# tinyJTAG-v10.net
KiCad netlist of a schematic drawn in EAGLE
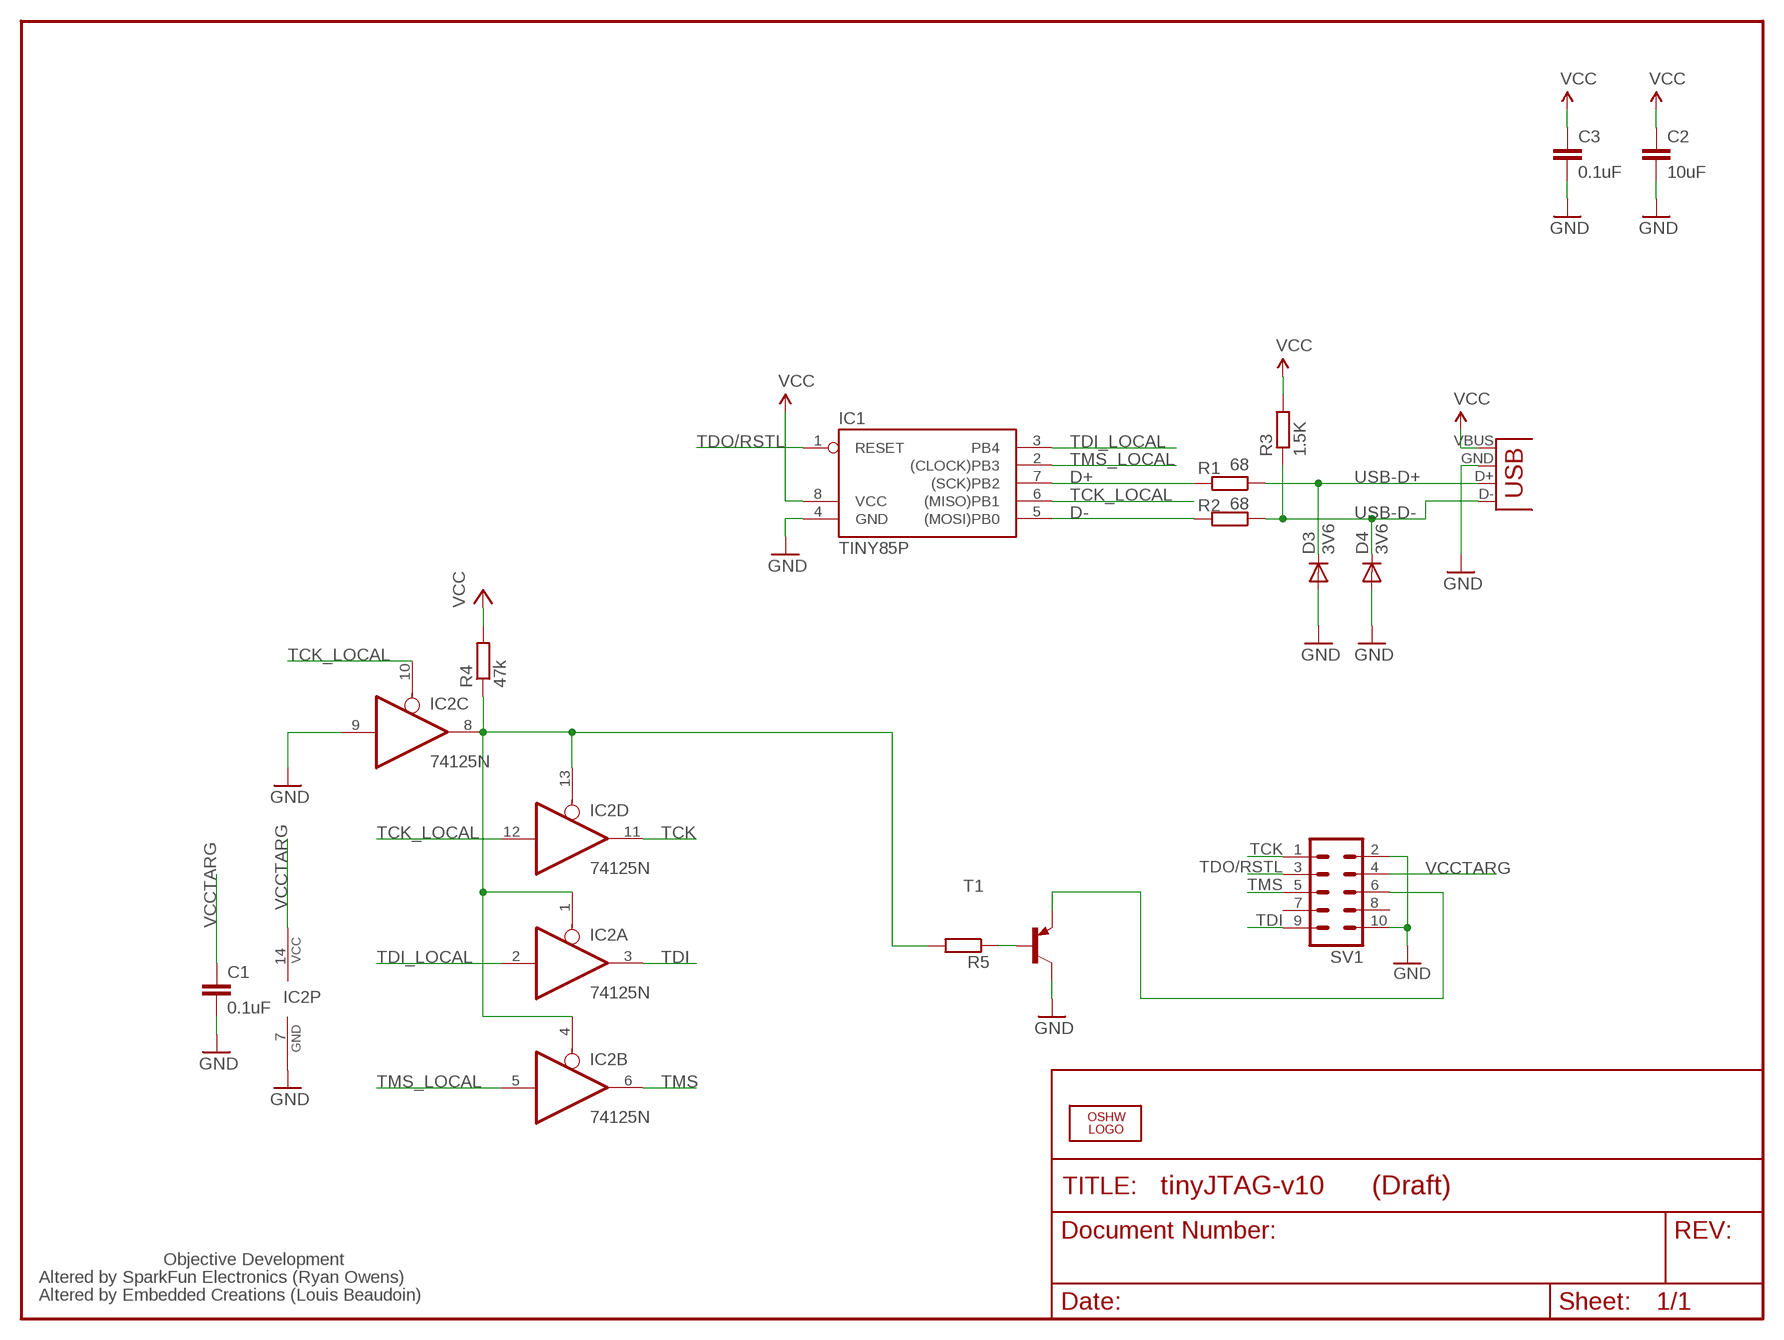
[diagram p0: schematic, sheet 1]

(export (version "E")
  (design (tool "Eeschema 10.0.6"))
  (components
    (comp (ref "C1")
      (value "0.1uF")
      (footprint "eagle-import:CAP-PTH-SMALL2")
      (libsource (lib "eagle-import") (part "CAPPTH2"))
    )
    (comp (ref "C2")
      (value "10uF")
      (footprint "eagle-import:C025-025X050")
      (libsource (lib "eagle-import") (part "C-EU025-025X050"))
    )
    (comp (ref "C3")
      (value "0.1uF")
      (footprint "eagle-import:CAP-PTH-SMALL")
      (libsource (lib "eagle-import") (part "CAPPTH"))
    )
    (comp (ref "D3")
      (value "3V6")
      (footprint "eagle-import:D-2.5")
      (libsource (lib "eagle-import") (part "DIODE-D-2.5"))
    )
    (comp (ref "D4")
      (value "3V6")
      (footprint "eagle-import:D-5")
      (libsource (lib "eagle-import") (part "DIODE-D-5"))
    )
    (comp (ref "IC1")
      (value "TINY85P")
      (footprint "eagle-import:DIL08")
      (libsource (lib "eagle-import") (part "TINY85P"))
    )
    (comp (ref "IC2")
      (value "74125N")
      (footprint "eagle-import:DIL14")
      (libsource (lib "eagle-import") (part "74125N"))
    )
    (comp (ref "LOGO1")
      (value "OSHW_LOGO_FILLX0150-NT")
      (footprint "eagle-import:OSHW_FILLX150_NOTEXT")
      (libsource (lib "eagle-import") (part "OSHW_LOGO_FILLX0150-NT"))
    )
    (comp (ref "R1")
      (value "68")
      (footprint "eagle-import:0207_2V")
      (libsource (lib "eagle-import") (part "R-EU_0207/2V"))
    )
    (comp (ref "R2")
      (value "68")
      (footprint "eagle-import:0207_2V")
      (libsource (lib "eagle-import") (part "R-EU_0207/2V"))
    )
    (comp (ref "R3")
      (value "1.5K")
      (footprint "eagle-import:0207_2V")
      (libsource (lib "eagle-import") (part "R-EU_0207/2V"))
    )
    (comp (ref "R4")
      (value "47k")
      (footprint "eagle-import:0207_7")
      (libsource (lib "eagle-import") (part "R-EU_0207/7"))
    )
    (comp (ref "R5")
      (value "R-EU_0207/7")
      (footprint "eagle-import:0207_7")
      (libsource (lib "eagle-import") (part "R-EU_0207/7"))
    )
    (comp (ref "SV1")
      (value "ML10")
      (footprint "eagle-import:ML10")
      (libsource (lib "eagle-import") (part "ML10"))
    )
    (comp (ref "T1")
      (value "BC327-16-PNP-TO92-EBC")
      (footprint "eagle-import:TO92-EBC")
      (libsource (lib "eagle-import") (part "-PNP-TO92-EBCBC327-16"))
    )
    (comp (ref "X1")
      (value "USB-A-H")
      (footprint "eagle-import:USB-A-H")
      (libsource (lib "eagle-import") (part "USB-A-H"))
    )
  )
  (nets
    (net (code "1") (name "/D+") (class "Default")
      (node (ref "IC1") (pin "7") (pinfunction "(SCK)PB2_7") (pintype "bidirectional"))
      (node (ref "R1") (pin "2") (pinfunction "2_2") (pintype "passive"))
    )
    (net (code "2") (name "/D-") (class "Default")
      (node (ref "IC1") (pin "5") (pinfunction "(MOSI)PB0_5") (pintype "bidirectional"))
      (node (ref "R2") (pin "2") (pinfunction "2_2") (pintype "passive"))
    )
    (net (code "3") (name "/TCK") (class "Default")
      (node (ref "IC2") (pin "11") (pinfunction "O_11") (pintype "tri_state"))
      (node (ref "SV1") (pin "1") (pinfunction "1_1") (pintype "passive"))
    )
    (net (code "4") (name "/TCK_LOCAL") (class "Default")
      (node (ref "IC1") (pin "6") (pinfunction "(MISO)PB1_6") (pintype "bidirectional"))
      (node (ref "IC2") (pin "10") (pinfunction "OE_10") (pintype "input"))
      (node (ref "IC2") (pin "12") (pinfunction "I_12") (pintype "input"))
    )
    (net (code "5") (name "/TDI") (class "Default")
      (node (ref "IC2") (pin "3") (pinfunction "O_3") (pintype "tri_state"))
      (node (ref "SV1") (pin "9") (pinfunction "9_9") (pintype "passive"))
    )
    (net (code "6") (name "/TDI_LOCAL") (class "Default")
      (node (ref "IC1") (pin "3") (pinfunction "PB4_3") (pintype "bidirectional"))
      (node (ref "IC2") (pin "2") (pinfunction "I_2") (pintype "input"))
    )
    (net (code "7") (name "/TDO{slash}RSTL") (class "Default")
      (node (ref "IC1") (pin "1") (pinfunction "RESET_1") (pintype "input"))
      (node (ref "SV1") (pin "3") (pinfunction "3_3") (pintype "passive"))
    )
    (net (code "8") (name "/TMS") (class "Default")
      (node (ref "IC2") (pin "6") (pinfunction "O_6") (pintype "tri_state"))
      (node (ref "SV1") (pin "5") (pinfunction "5_5") (pintype "passive"))
    )
    (net (code "9") (name "/TMS_LOCAL") (class "Default")
      (node (ref "IC1") (pin "2") (pinfunction "(CLOCK)PB3_2") (pintype "bidirectional"))
      (node (ref "IC2") (pin "5") (pinfunction "I_5") (pintype "input"))
    )
    (net (code "10") (name "/USB-D+") (class "Default")
      (node (ref "D3") (pin "C") (pinfunction "C_C") (pintype "passive"))
      (node (ref "R1") (pin "1") (pinfunction "1_1") (pintype "passive"))
      (node (ref "X1") (pin "D+") (pinfunction "D-_D+") (pintype "bidirectional"))
    )
    (net (code "11") (name "/USB-D-") (class "Default")
      (node (ref "D4") (pin "C") (pinfunction "C_C") (pintype "passive"))
      (node (ref "R2") (pin "1") (pinfunction "1_1") (pintype "passive"))
      (node (ref "R3") (pin "1") (pinfunction "1_1") (pintype "passive"))
      (node (ref "X1") (pin "D-") (pinfunction "D+_D-") (pintype "bidirectional"))
    )
    (net (code "12") (name "/VCCTARG") (class "Default")
      (node (ref "C1") (pin "1") (pinfunction "1_1") (pintype "passive"))
      (node (ref "IC2") (pin "14") (pinfunction "VCC_14") (pintype "power_in"))
      (node (ref "SV1") (pin "4") (pinfunction "4_4") (pintype "passive"))
    )
    (net (code "13") (name "GND") (class "Default")
      (node (ref "C1") (pin "2") (pinfunction "2_2") (pintype "passive"))
      (node (ref "C2") (pin "2") (pinfunction "2_2") (pintype "passive"))
      (node (ref "C3") (pin "2") (pinfunction "2_2") (pintype "passive"))
      (node (ref "D3") (pin "A") (pinfunction "A_A") (pintype "passive"))
      (node (ref "D4") (pin "A") (pinfunction "A_A") (pintype "passive"))
      (node (ref "IC1") (pin "4") (pinfunction "GND_4") (pintype "power_in"))
      (node (ref "IC2") (pin "7") (pinfunction "GND_7") (pintype "power_in"))
      (node (ref "IC2") (pin "9") (pinfunction "I_9") (pintype "input"))
      (node (ref "SV1") (pin "10") (pinfunction "10_10") (pintype "passive"))
      (node (ref "SV1") (pin "2") (pinfunction "2_2") (pintype "passive"))
      (node (ref "T1") (pin "C") (pinfunction "C_C") (pintype "passive"))
      (node (ref "X1") (pin "GND") (pinfunction "VBUS_GND") (pintype "bidirectional"))
    )
    (net (code "14") (name "Net-(IC2A-OE)") (class "Default")
      (node (ref "IC2") (pin "1") (pinfunction "OE_1") (pintype "input"))
      (node (ref "IC2") (pin "13") (pinfunction "OE_13") (pintype "input"))
      (node (ref "IC2") (pin "4") (pinfunction "OE_4") (pintype "input"))
      (node (ref "IC2") (pin "8") (pinfunction "O_8") (pintype "tri_state"))
      (node (ref "R4") (pin "1") (pinfunction "1_1") (pintype "passive"))
      (node (ref "R5") (pin "2") (pinfunction "2_2") (pintype "passive"))
    )
    (net (code "15") (name "Net-(R5-Pad1)") (class "Default")
      (node (ref "R5") (pin "1") (pinfunction "1_1") (pintype "passive"))
      (node (ref "T1") (pin "B") (pinfunction "B_B") (pintype "passive"))
    )
    (net (code "16") (name "Net-(SV1-Pad6)") (class "Default")
      (node (ref "SV1") (pin "6") (pinfunction "6_6") (pintype "passive"))
      (node (ref "T1") (pin "E") (pinfunction "E_E") (pintype "passive"))
    )
    (net (code "17") (name "VCC") (class "Default")
      (node (ref "C2") (pin "1") (pinfunction "1_1") (pintype "passive"))
      (node (ref "C3") (pin "1") (pinfunction "1_1") (pintype "passive"))
      (node (ref "IC1") (pin "8") (pinfunction "VCC_8") (pintype "power_in"))
      (node (ref "R3") (pin "2") (pinfunction "2_2") (pintype "passive"))
      (node (ref "R4") (pin "2") (pinfunction "2_2") (pintype "passive"))
      (node (ref "X1") (pin "VBUS") (pinfunction "GND_VBUS") (pintype "bidirectional"))
    )
    (net (code "18") (name "unconnected-(SV1-Pad7)") (class "Default")
      (node (ref "SV1") (pin "7") (pinfunction "7_7") (pintype "passive"))
    )
    (net (code "19") (name "unconnected-(SV1-Pad8)") (class "Default")
      (node (ref "SV1") (pin "8") (pinfunction "8_8") (pintype "passive"))
    )
  )
)
